# design.net
KiCad netlist of a schematic drawn in Altium Designer
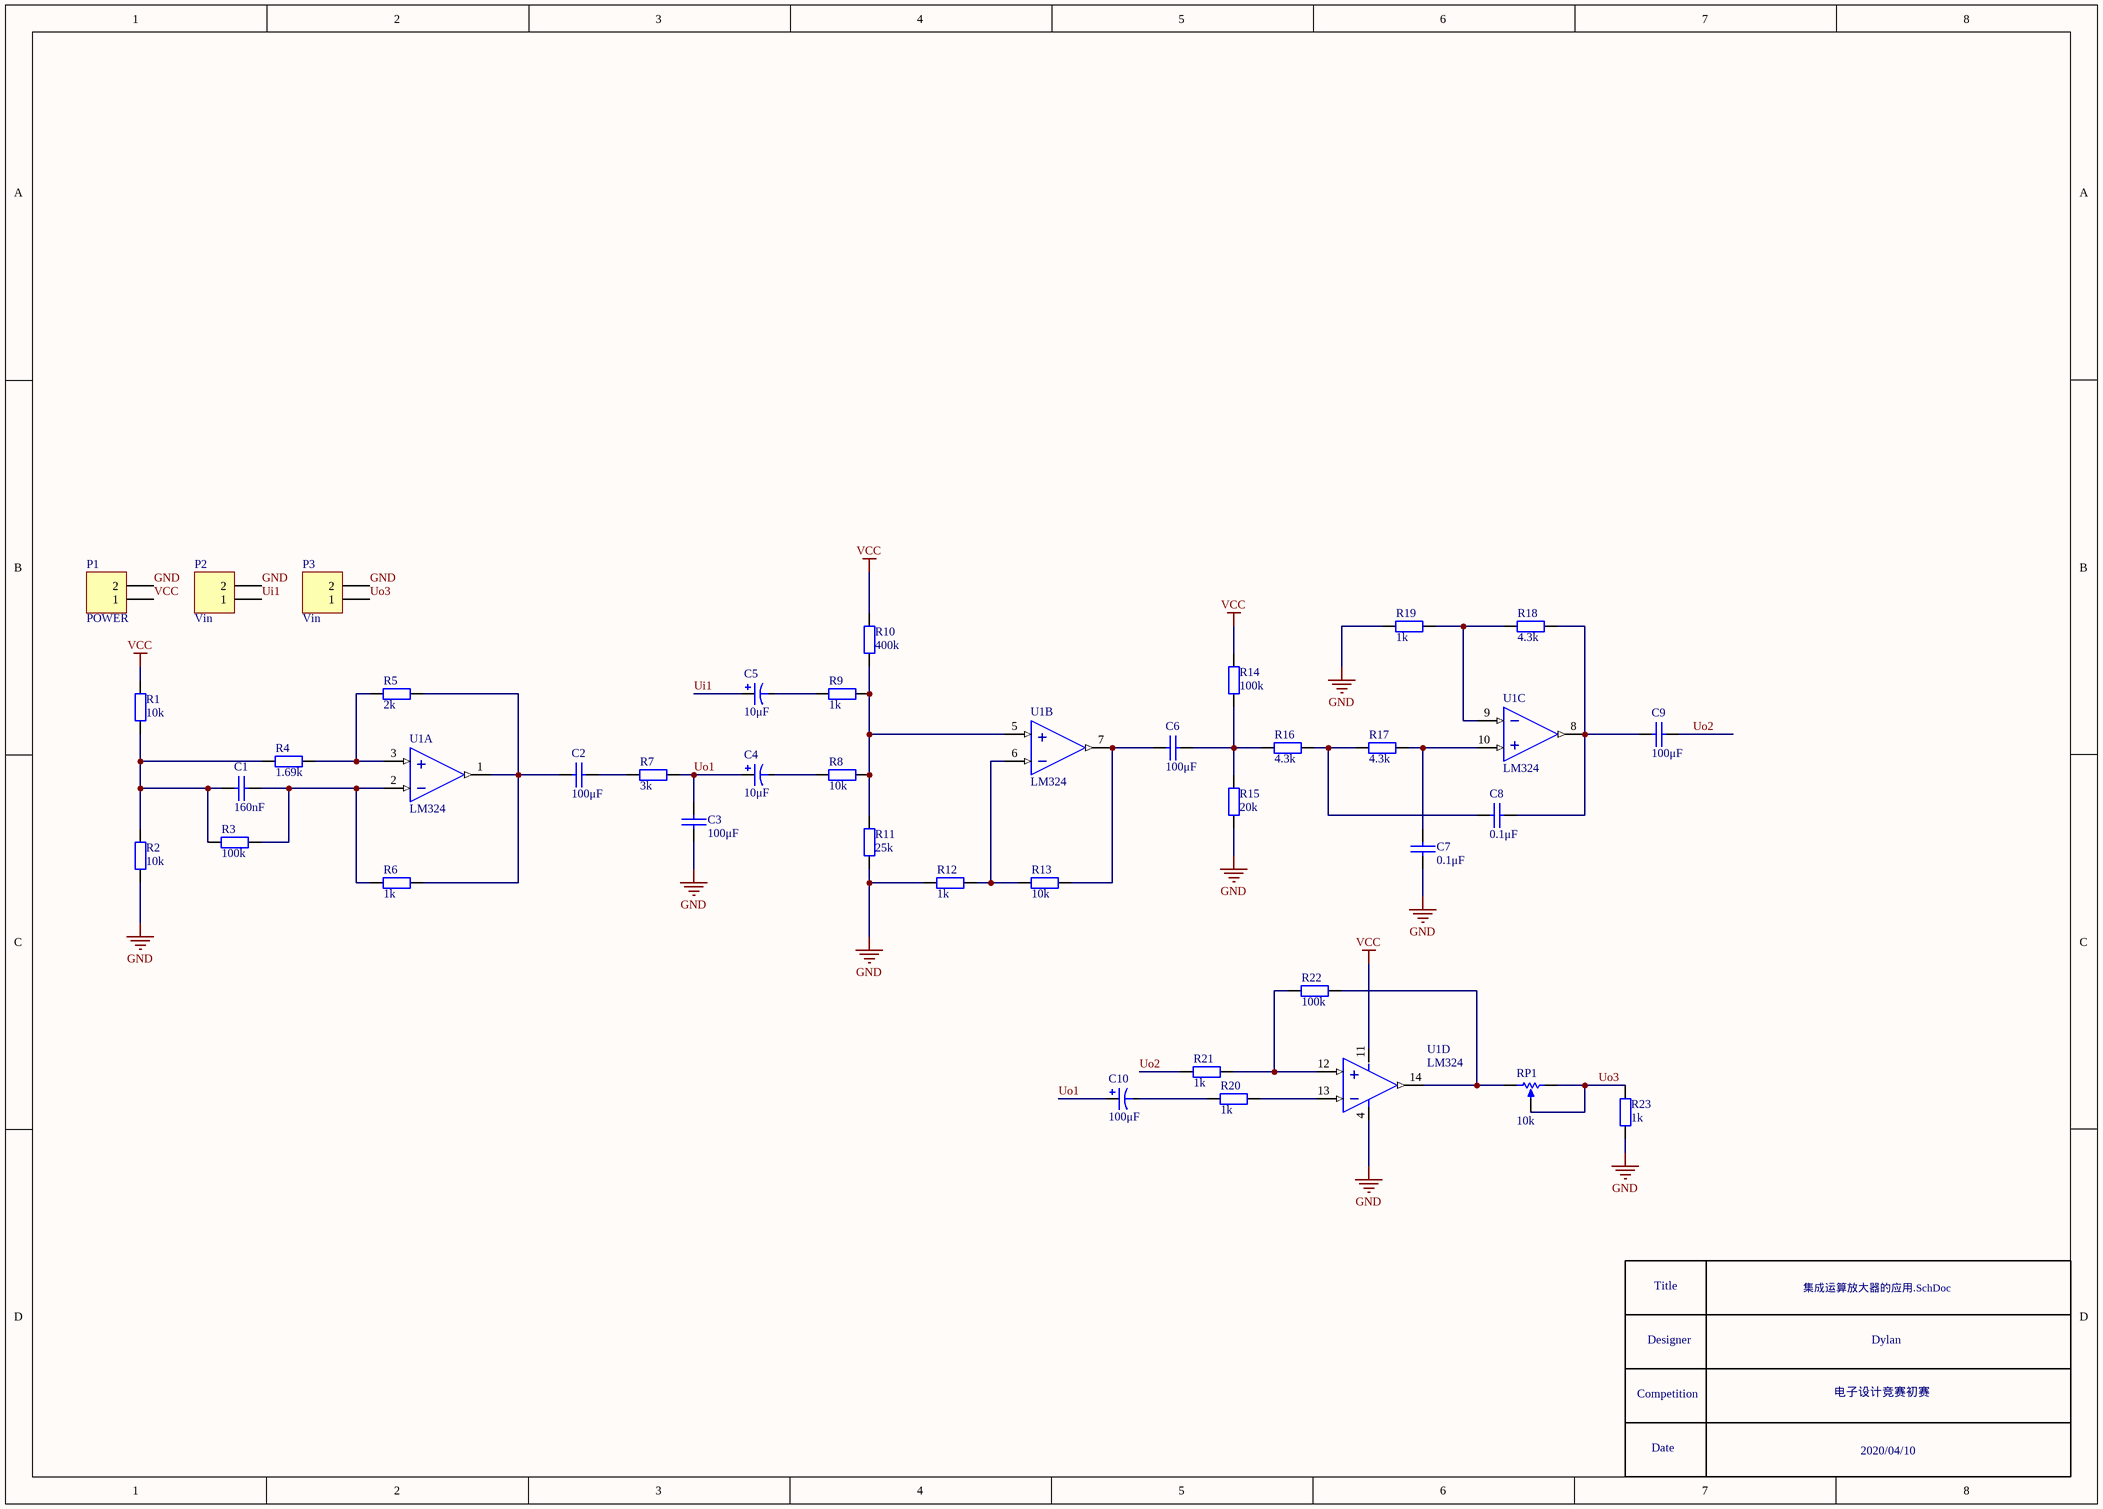
[diagram p0: 集成运算放大器的应用.SchDoc]

(export (version "E")
  (design (tool "Eeschema 10.0.6"))
  (components
    (comp (ref "C1")
      (value "160nF")
      (footprint "0805C")
      (description "Capacitor")
      (libsource (lib "xqj") (part "CAP"))
    )
    (comp (ref "C2")
      (value "100μF")
      (footprint "0805C")
      (description "Capacitor")
      (libsource (lib "xqj") (part "CAP"))
    )
    (comp (ref "C3")
      (value "100μF")
      (footprint "0805C")
      (description "Capacitor")
      (libsource (lib "xqj") (part "CAP"))
    )
    (comp (ref "C4")
      (value "10μF")
      (footprint "CAP.1/.2")
      (description "Capacitor")
      (libsource (lib "xqj") (part "CAP+"))
    )
    (comp (ref "C5")
      (value "10μF")
      (footprint "CAP.1/.2")
      (description "Capacitor")
      (libsource (lib "xqj") (part "CAP+"))
    )
    (comp (ref "C6")
      (value "100μF")
      (footprint "0805C")
      (description "Capacitor")
      (libsource (lib "xqj") (part "CAP"))
    )
    (comp (ref "C7")
      (value "0.1μF")
      (footprint "0805C")
      (description "Capacitor")
      (libsource (lib "xqj") (part "CAP"))
    )
    (comp (ref "C8")
      (value "0.1μF")
      (footprint "0805C")
      (description "Capacitor")
      (libsource (lib "xqj") (part "CAP"))
    )
    (comp (ref "C9")
      (value "100μF")
      (footprint "0805C")
      (description "Capacitor")
      (libsource (lib "xqj") (part "CAP"))
    )
    (comp (ref "C10")
      (value "100μF")
      (footprint "CAP.1/.2")
      (description "Capacitor")
      (libsource (lib "xqj") (part "CAP+"))
    )
    (comp (ref "P1")
      (value "POWER")
      (footprint "HDR1X2")
      (description "Header, 2-Pin")
      (fields (field (name "PUBLISHER") "Altium Limited"))
      (libsource (lib "xqj") (part "Header 2"))
    )
    (comp (ref "P2")
      (value "Vin")
      (footprint "HDR1X2")
      (description "Header, 2-Pin")
      (fields (field (name "PUBLISHER") "Altium Limited"))
      (libsource (lib "xqj") (part "Header 2"))
    )
    (comp (ref "P3")
      (value "Vin")
      (footprint "HDR1X2")
      (description "Header, 2-Pin")
      (fields (field (name "PUBLISHER") "Altium Limited"))
      (libsource (lib "xqj") (part "Header 2"))
    )
    (comp (ref "R1")
      (value "10k")
      (footprint "0805R")
      (description "Resistor")
      (libsource (lib "") (part "Res_2"))
    )
    (comp (ref "R2")
      (value "10k")
      (footprint "0805R")
      (description "Resistor")
      (libsource (lib "") (part "Res_2"))
    )
    (comp (ref "R3")
      (value "100k")
      (footprint "0805R")
      (description "Resistor")
      (libsource (lib "") (part "Res_1"))
    )
    (comp (ref "R4")
      (value "1.69k")
      (footprint "0805R")
      (description "Resistor")
      (libsource (lib "") (part "Res_1"))
    )
    (comp (ref "R5")
      (value "2k")
      (footprint "0805R")
      (description "Resistor")
      (libsource (lib "") (part "Res_1"))
    )
    (comp (ref "R6")
      (value "1k")
      (footprint "0805R")
      (description "Resistor")
      (libsource (lib "") (part "Res_1"))
    )
    (comp (ref "R7")
      (value "3k")
      (footprint "0805R")
      (description "Resistor")
      (libsource (lib "") (part "Res_1"))
    )
    (comp (ref "R8")
      (value "10k")
      (footprint "0805R")
      (description "Resistor")
      (libsource (lib "xqj") (part "Res"))
    )
    (comp (ref "R9")
      (value "1k")
      (footprint "0805R")
      (description "Resistor")
      (libsource (lib "xqj") (part "Res"))
    )
    (comp (ref "R10")
      (value "400k")
      (footprint "0805R")
      (description "Resistor")
      (libsource (lib "") (part "Res_2"))
    )
    (comp (ref "R11")
      (value "25k")
      (footprint "0805R")
      (description "Resistor")
      (libsource (lib "") (part "Res_2"))
    )
    (comp (ref "R12")
      (value "1k")
      (footprint "0805R")
      (description "Resistor")
      (libsource (lib "xqj") (part "Res"))
    )
    (comp (ref "R13")
      (value "10k")
      (footprint "0805R")
      (description "Resistor")
      (libsource (lib "xqj") (part "Res"))
    )
    (comp (ref "R14")
      (value "100k")
      (footprint "0805R")
      (description "Resistor")
      (libsource (lib "") (part "Res_2"))
    )
    (comp (ref "R15")
      (value "20k")
      (footprint "0805R")
      (description "Resistor")
      (libsource (lib "") (part "Res_2"))
    )
    (comp (ref "R16")
      (value "4.3k")
      (footprint "0805R")
      (description "Resistor")
      (libsource (lib "xqj") (part "Res"))
    )
    (comp (ref "R17")
      (value "4.3k")
      (footprint "0805R")
      (description "Resistor")
      (libsource (lib "xqj") (part "Res"))
    )
    (comp (ref "R18")
      (value "4.3k")
      (footprint "0805R")
      (description "Resistor")
      (libsource (lib "xqj") (part "Res"))
    )
    (comp (ref "R19")
      (value "1k")
      (footprint "0805R")
      (description "Resistor")
      (libsource (lib "xqj") (part "Res"))
    )
    (comp (ref "R20")
      (value "1k")
      (footprint "0805R")
      (description "Resistor")
      (libsource (lib "xqj") (part "Res"))
    )
    (comp (ref "R21")
      (value "1k")
      (footprint "0805R")
      (description "Resistor")
      (libsource (lib "xqj") (part "Res"))
    )
    (comp (ref "R22")
      (value "100k")
      (footprint "0805R")
      (description "Resistor")
      (libsource (lib "xqj") (part "Res"))
    )
    (comp (ref "R23")
      (value "1k")
      (footprint "0805R")
      (description "Resistor")
      (libsource (lib "") (part "Res_3"))
    )
    (comp (ref "RP1")
      (value "10k")
      (footprint "3296")
      (description "Resistor")
      (libsource (lib "xqj") (part "RPOT1"))
    )
    (comp (ref "U1") (value "LM324") (footprint "SO-14") (libsource (lib "xqj") (part "LM324")))
  )
  (nets
    (net (code "1") (name "/Ui1") (class "Default")
      (node (ref "C5") (pin "1") (pinfunction "1_1") (pintype "passive"))
      (node (ref "P2") (pin "1") (pinfunction "1_1") (pintype "passive"))
    )
    (net (code "2") (name "/Uo1") (class "Default")
      (node (ref "C10") (pin "1") (pinfunction "1_1") (pintype "passive"))
      (node (ref "C3") (pin "2") (pinfunction "2_2") (pintype "passive"))
      (node (ref "C4") (pin "1") (pinfunction "1_1") (pintype "passive"))
      (node (ref "R7") (pin "2") (pinfunction "2_2") (pintype "passive"))
    )
    (net (code "3") (name "/Uo2") (class "Default")
      (node (ref "C9") (pin "2") (pinfunction "2_2") (pintype "passive"))
      (node (ref "R21") (pin "2") (pinfunction "2_2") (pintype "passive"))
    )
    (net (code "4") (name "/Uo3") (class "Default")
      (node (ref "P3") (pin "1") (pinfunction "1_1") (pintype "passive"))
      (node (ref "R23") (pin "1") (pinfunction "1_1") (pintype "passive"))
      (node (ref "RP1") (pin "2") (pinfunction "BOT_2") (pintype "passive"))
      (node (ref "RP1") (pin "3") (pinfunction "TAP_3") (pintype "passive"))
    )
    (net (code "5") (name "GND") (class "Default")
      (node (ref "C3") (pin "1") (pinfunction "1_1") (pintype "passive"))
      (node (ref "C7") (pin "1") (pinfunction "1_1") (pintype "passive"))
      (node (ref "P1") (pin "2") (pinfunction "2_2") (pintype "passive"))
      (node (ref "P2") (pin "2") (pinfunction "2_2") (pintype "passive"))
      (node (ref "P3") (pin "2") (pinfunction "2_2") (pintype "passive"))
      (node (ref "R11") (pin "1") (pinfunction "1_1") (pintype "passive"))
      (node (ref "R12") (pin "2") (pinfunction "2_2") (pintype "passive"))
      (node (ref "R15") (pin "1") (pinfunction "1_1") (pintype "passive"))
      (node (ref "R19") (pin "2") (pinfunction "2_2") (pintype "passive"))
      (node (ref "R2") (pin "1") (pinfunction "1_1") (pintype "passive"))
      (node (ref "R23") (pin "2") (pinfunction "2_2") (pintype "passive"))
      (node (ref "U1") (pin "4") (pinfunction "VCC_4") (pintype "passive"))
    )
    (net (code "6") (name "Net-(C1-Pad1)") (class "Default")
      (node (ref "C1") (pin "1") (pinfunction "1_1") (pintype "passive"))
      (node (ref "R1") (pin "1") (pinfunction "1_1") (pintype "passive"))
      (node (ref "R2") (pin "2") (pinfunction "2_2") (pintype "passive"))
      (node (ref "R3") (pin "1") (pinfunction "1_1") (pintype "passive"))
      (node (ref "R4") (pin "1") (pinfunction "1_1") (pintype "passive"))
    )
    (net (code "7") (name "Net-(C2-Pad2)") (class "Default")
      (node (ref "C2") (pin "2") (pinfunction "2_2") (pintype "passive"))
      (node (ref "R7") (pin "1") (pinfunction "1_1") (pintype "passive"))
    )
    (net (code "8") (name "Net-(C4-Pad2)") (class "Default")
      (node (ref "C4") (pin "2") (pinfunction "2_2") (pintype "passive"))
      (node (ref "R8") (pin "2") (pinfunction "2_2") (pintype "passive"))
    )
    (net (code "9") (name "Net-(C5-Pad2)") (class "Default")
      (node (ref "C5") (pin "2") (pinfunction "2_2") (pintype "passive"))
      (node (ref "R9") (pin "2") (pinfunction "2_2") (pintype "passive"))
    )
    (net (code "10") (name "Net-(C6-Pad2)") (class "Default")
      (node (ref "C6") (pin "2") (pinfunction "2_2") (pintype "passive"))
      (node (ref "R14") (pin "1") (pinfunction "1_1") (pintype "passive"))
      (node (ref "R15") (pin "2") (pinfunction "2_2") (pintype "passive"))
      (node (ref "R16") (pin "2") (pinfunction "2_2") (pintype "passive"))
    )
    (net (code "11") (name "Net-(C8-Pad1)") (class "Default")
      (node (ref "C8") (pin "1") (pinfunction "1_1") (pintype "passive"))
      (node (ref "R16") (pin "1") (pinfunction "1_1") (pintype "passive"))
      (node (ref "R17") (pin "2") (pinfunction "2_2") (pintype "passive"))
    )
    (net (code "12") (name "Net-(C10-Pad2)") (class "Default")
      (node (ref "C10") (pin "2") (pinfunction "2_2") (pintype "passive"))
      (node (ref "R20") (pin "2") (pinfunction "2_2") (pintype "passive"))
    )
    (net (code "13") (name "Net-(RP1-TOP)") (class "Default")
      (node (ref "R22") (pin "1") (pinfunction "1_1") (pintype "passive"))
      (node (ref "RP1") (pin "1") (pinfunction "TOP_1") (pintype "passive"))
      (node (ref "U1") (pin "14") (pinfunction "4OUT_14") (pintype "output"))
    )
    (net (code "14") (name "Net-(U1A-1IN+)") (class "Default")
      (node (ref "R4") (pin "2") (pinfunction "2_2") (pintype "passive"))
      (node (ref "R5") (pin "1") (pinfunction "1_1") (pintype "passive"))
      (node (ref "U1") (pin "3") (pinfunction "1IN+_3") (pintype "input"))
    )
    (net (code "15") (name "Net-(U1A-1IN-)") (class "Default")
      (node (ref "C1") (pin "2") (pinfunction "2_2") (pintype "passive"))
      (node (ref "R3") (pin "2") (pinfunction "2_2") (pintype "passive"))
      (node (ref "R6") (pin "1") (pinfunction "1_1") (pintype "passive"))
      (node (ref "U1") (pin "2") (pinfunction "1IN-_2") (pintype "input"))
    )
    (net (code "16") (name "Net-(U1A-OUT1)") (class "Default")
      (node (ref "C2") (pin "1") (pinfunction "1_1") (pintype "passive"))
      (node (ref "R5") (pin "2") (pinfunction "2_2") (pintype "passive"))
      (node (ref "R6") (pin "2") (pinfunction "2_2") (pintype "passive"))
      (node (ref "U1") (pin "1") (pinfunction "OUT1_1") (pintype "output"))
    )
    (net (code "17") (name "Net-(U1B-2IN+)") (class "Default")
      (node (ref "R10") (pin "1") (pinfunction "1_1") (pintype "passive"))
      (node (ref "R11") (pin "2") (pinfunction "2_2") (pintype "passive"))
      (node (ref "R8") (pin "1") (pinfunction "1_1") (pintype "passive"))
      (node (ref "R9") (pin "1") (pinfunction "1_1") (pintype "passive"))
      (node (ref "U1") (pin "5") (pinfunction "2IN+_5") (pintype "input"))
    )
    (net (code "18") (name "Net-(U1B-2IN-)") (class "Default")
      (node (ref "R12") (pin "1") (pinfunction "1_1") (pintype "passive"))
      (node (ref "R13") (pin "2") (pinfunction "2_2") (pintype "passive"))
      (node (ref "U1") (pin "6") (pinfunction "2IN-_6") (pintype "input"))
    )
    (net (code "19") (name "Net-(U1B-2OUT)") (class "Default")
      (node (ref "C6") (pin "1") (pinfunction "1_1") (pintype "passive"))
      (node (ref "R13") (pin "1") (pinfunction "1_1") (pintype "passive"))
      (node (ref "U1") (pin "7") (pinfunction "2OUT_7") (pintype "output"))
    )
    (net (code "20") (name "Net-(U1C-3N+)") (class "Default")
      (node (ref "C7") (pin "2") (pinfunction "2_2") (pintype "passive"))
      (node (ref "R17") (pin "1") (pinfunction "1_1") (pintype "passive"))
      (node (ref "U1") (pin "10") (pinfunction "3N+_10") (pintype "input"))
    )
    (net (code "21") (name "Net-(U1C-3N-)") (class "Default")
      (node (ref "R18") (pin "2") (pinfunction "2_2") (pintype "passive"))
      (node (ref "R19") (pin "1") (pinfunction "1_1") (pintype "passive"))
      (node (ref "U1") (pin "9") (pinfunction "3N-_9") (pintype "input"))
    )
    (net (code "22") (name "Net-(U1C-3OUT)") (class "Default")
      (node (ref "C8") (pin "2") (pinfunction "2_2") (pintype "passive"))
      (node (ref "C9") (pin "1") (pinfunction "1_1") (pintype "passive"))
      (node (ref "R18") (pin "1") (pinfunction "1_1") (pintype "passive"))
      (node (ref "U1") (pin "8") (pinfunction "3OUT_8") (pintype "output"))
    )
    (net (code "23") (name "Net-(U1D-4IN+)") (class "Default")
      (node (ref "R21") (pin "1") (pinfunction "1_1") (pintype "passive"))
      (node (ref "R22") (pin "2") (pinfunction "2_2") (pintype "passive"))
      (node (ref "U1") (pin "12") (pinfunction "4IN+_12") (pintype "input"))
    )
    (net (code "24") (name "Net-(U1D-4IN-)") (class "Default")
      (node (ref "R20") (pin "1") (pinfunction "1_1") (pintype "passive"))
      (node (ref "U1") (pin "13") (pinfunction "4IN-_13") (pintype "input"))
    )
    (net (code "25") (name "VCC") (class "Default")
      (node (ref "P1") (pin "1") (pinfunction "1_1") (pintype "passive"))
      (node (ref "R1") (pin "2") (pinfunction "2_2") (pintype "passive"))
      (node (ref "R10") (pin "2") (pinfunction "2_2") (pintype "passive"))
      (node (ref "R14") (pin "2") (pinfunction "2_2") (pintype "passive"))
      (node (ref "U1") (pin "11") (pinfunction "GND_11") (pintype "passive"))
    )
  )
)
